# 1_Airframe-Power_1.net
KiCad netlist of a schematic drawn in Altium Designer
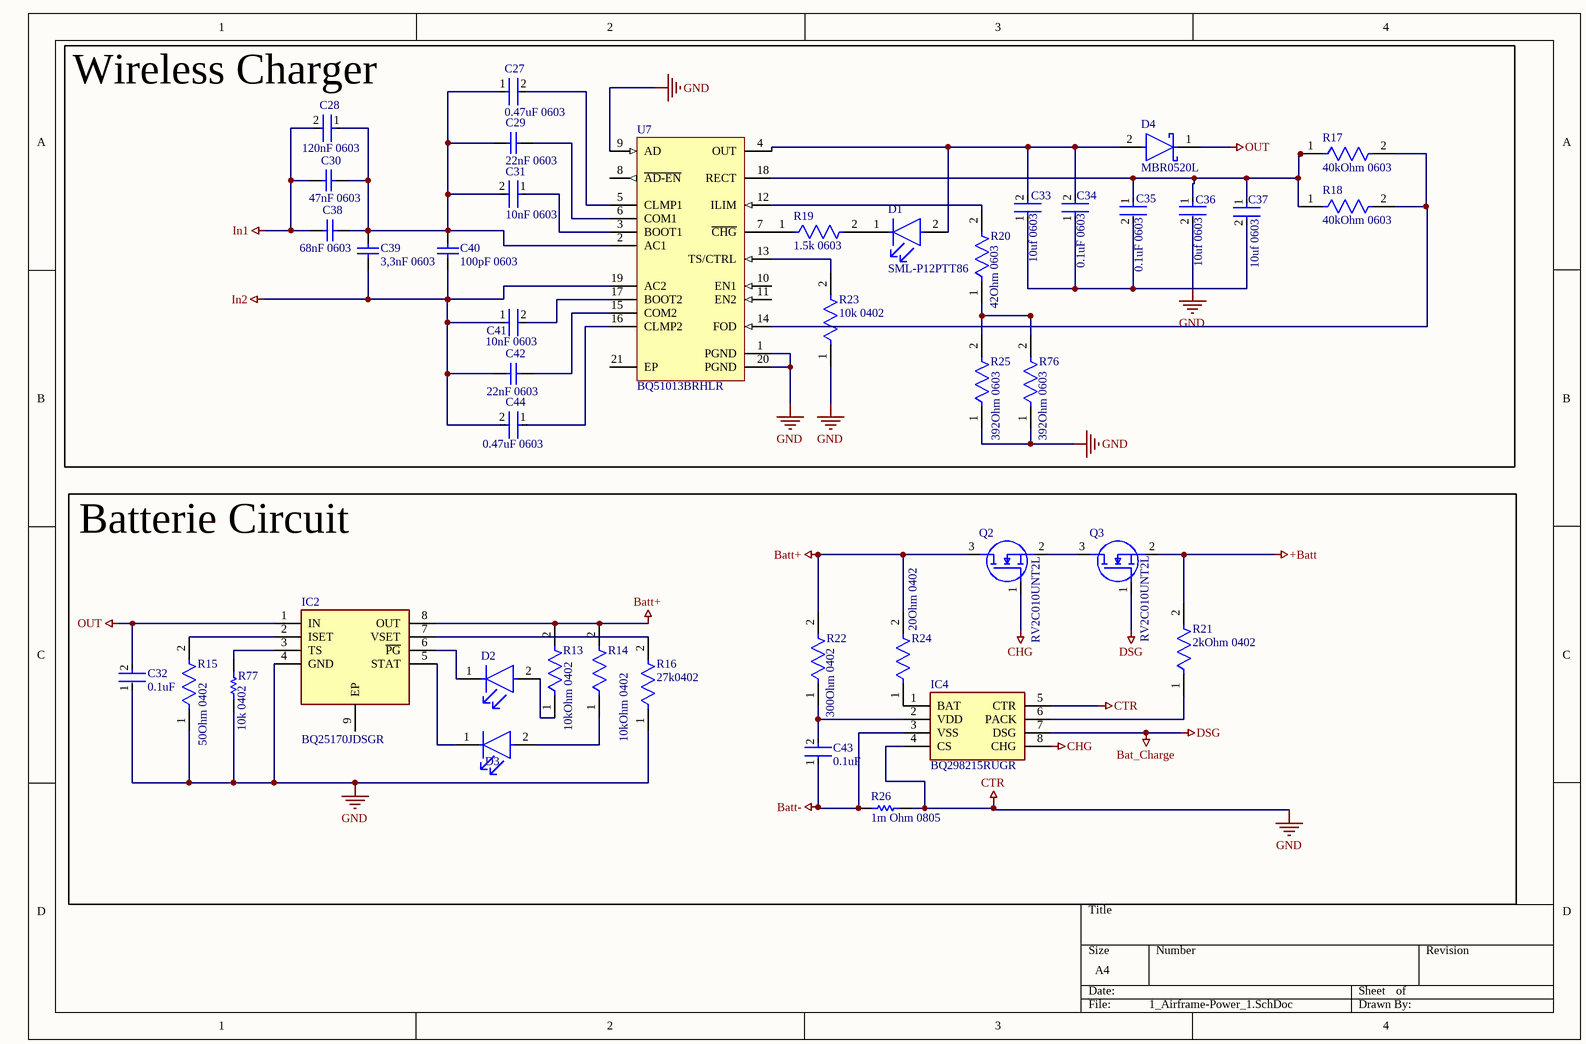
[diagram p0: 1_Airframe-Power_1.SchDoc]

(export (version "E")
  (design (tool "Eeschema 10.0.6"))
  (components
    (comp (ref "C27")
      (value "0.47uF 0603")
      (footprint "FP-GRM188-0_1-e0_2_0_5-IPC_A")
      (description "Chip Multilayer Ceramic Capacitors for General Purpose, 0603, 0.47uF, X7R, 15%, 10%, 16V")
      (fields (field (name "VOLTAGE") "16V") (field (name "TOLERANCE") "10%"))
      (libsource (lib "Altium Content Vault") (part "11868f565c42a9108669ba33697ecf6"))
    )
    (comp (ref "C28")
      (value "120nF 0603")
      (footprint "FP-C0603C-CF-MFG")
      (description "0603 C 120nF Ceramic Multilayer Capacitor; 50 V; +125degC; X7R Dielec; +/-10%")
      (fields (field (name "MANUFACTURER") "KEMET") (field (name "TOLERANCE") "0.1"))
      (libsource (lib "Altium Content Vault") (part "b4654b650e69147ec39a6b967a45e02"))
    )
    (comp (ref "C29")
      (value "22nF 0603")
      (footprint "CAPC1608X90X35ML10T15")
      (fields (field (name "MANUFACTURER") "Murata") (field (name "PART NUMBER") "GRM188R71H223KA01D"))
      (libsource (lib "Altium Content Vault") (part "CAP"))
    )
    (comp (ref "C30")
      (value "47nF 0603")
      (footprint "CAPC1608X90X35ML10T15")
      (fields (field (name "MANUFACTURER") "Murata") (field (name "PART NUMBER") "GRM188R71H473KA61D"))
      (libsource (lib "Altium Content Vault") (part "CAP"))
    )
    (comp (ref "C31")
      (value "10nF 0603")
      (footprint "FP-CC0603-DA-MFG")
      (description "CAP CER 10000PF 50V X7R 0603")
      (fields (field (name "TOLERANCE") "0.1") (field (name "MANUFACTURER PART NUMBER") "CC0603KRX7R9BB103"))
      (libsource (lib "Altium Content Vault") (part "11868f565c42a9108669ba33697ecf6"))
    )
    (comp (ref "C32")
      (value "0.1uF")
      (footprint "FP-GRM15-MFG")
      (description "CAP CER 0.1UF 16V X7R 0402")
      (fields (field (name "MANUFACTURER PART NUMBER") "GRM155R71C104KA88D") (field (name "TOLERANCE") "10%"))
      (libsource (lib "Altium Content Vault") (part "236180d848d6139a670b325ea6854c9"))
    )
    (comp (ref "C33")
      (value "10uf 0603")
      (footprint "FP-GRM188-0_1-e0_2_0_55-IPC_C")
      (description "Chip Multilayer Ceramic Capacitors for General Purpose, 0603, 10uF, X5R, 15%, 20%, 6.3V")
      (fields (field (name "VOLTAGE") "6.3V") (field (name "TOLERANCE") "20%"))
      (libsource (lib "Altium Content Vault") (part "02cd4be3c70576c341d710602a673aa"))
    )
    (comp (ref "C34")
      (value "0.1uF 0603")
      (footprint "FP-C0603C-CF-MFG")
      (description "CAP CER 0.1UF 50V X7R 0603")
      (fields (field (name "TOLERANCE") "0.1") (field (name "MANUFACTURER") "KEMET"))
      (libsource (lib "Altium Content Vault") (part "b4654b650e69147ec39a6b967a45e02"))
    )
    (comp (ref "C35")
      (value "0.1uF 0603")
      (footprint "FP-C0603C-CF-MFG")
      (description "CAP CER 0.1UF 50V X7R 0603")
      (fields (field (name "TOLERANCE") "0.1") (field (name "MANUFACTURER") "KEMET"))
      (libsource (lib "Altium Content Vault") (part "b4654b650e69147ec39a6b967a45e02"))
    )
    (comp (ref "C36")
      (value "10uf 0603")
      (footprint "FP-GRM188-0_1-e0_2_0_55-IPC_C")
      (description "Chip Multilayer Ceramic Capacitors for General Purpose, 0603, 10uF, X5R, 15%, 20%, 6.3V")
      (fields (field (name "VOLTAGE") "6.3V") (field (name "TOLERANCE") "20%"))
      (libsource (lib "Altium Content Vault") (part "02cd4be3c70576c341d710602a673aa"))
    )
    (comp (ref "C37")
      (value "10uf 0603")
      (footprint "FP-GRM188-0_1-e0_2_0_55-IPC_C")
      (description "Chip Multilayer Ceramic Capacitors for General Purpose, 0603, 10uF, X5R, 15%, 20%, 6.3V")
      (fields (field (name "VOLTAGE") "6.3V") (field (name "TOLERANCE") "20%"))
      (libsource (lib "Altium Content Vault") (part "02cd4be3c70576c341d710602a673aa"))
    )
    (comp (ref "C38")
      (value "68nF 0603")
      (footprint "CAPC1608X90X35LL10T15")
      (fields (field (name "PART NUMBER") "GRM188R71H683KA93D") (field (name "MANUFACTURER") "Murata"))
      (libsource (lib "Altium Content Vault") (part "CAP"))
    )
    (comp (ref "C39")
      (value "3,3nF 0603")
      (footprint "CAPC1608X90X35LL10T15")
      (fields (field (name "MANUFACTURER") "Murata") (field (name "PART NUMBER") "GRM188R71H332KA01D"))
      (libsource (lib "Altium Content Vault") (part "CAP"))
    )
    (comp (ref "C40")
      (value "100pF 0603")
      (footprint "CAPC1608X90X35NL10T15")
      (fields (field (name "PART NUMBER") "GRM1885C1H101JA01D") (field (name "MANUFACTURER") "Murata"))
      (libsource (lib "Altium Content Vault") (part "CAP"))
    )
    (comp (ref "C41")
      (value "10nF 0603")
      (footprint "FP-CC0603-DA-MFG")
      (description "CAP CER 10000PF 50V X7R 0603")
      (fields (field (name "TOLERANCE") "0.1") (field (name "MANUFACTURER PART NUMBER") "CC0603KRX7R9BB103"))
      (libsource (lib "Altium Content Vault") (part "11868f565c42a9108669ba33697ecf6"))
    )
    (comp (ref "C42")
      (value "22nF 0603")
      (footprint "CAPC1608X90X35ML10T15")
      (fields (field (name "MANUFACTURER") "Murata") (field (name "PART NUMBER") "GRM188R71H223KA01D"))
      (libsource (lib "Altium Content Vault") (part "CAP"))
    )
    (comp (ref "C43")
      (value "0.1uF")
      (footprint "FP-GRM15-MFG")
      (description "CAP CER 0.1UF 16V X7R 0402")
      (fields (field (name "MANUFACTURER PART NUMBER") "GRM155R71C104KA88D") (field (name "TOLERANCE") "10%"))
      (libsource (lib "Altium Content Vault") (part "236180d848d6139a670b325ea6854c9"))
    )
    (comp (ref "C44")
      (value "0.47uF 0603")
      (footprint "FP-GRM188-0_1-e0_2_0_5-IPC_A")
      (description "Chip Multilayer Ceramic Capacitors for General Purpose, 0603, 0.47uF, X7R, 15%, 10%, 16V")
      (fields (field (name "VOLTAGE") "16V") (field (name "TOLERANCE") "10%"))
      (libsource (lib "Altium Content Vault") (part "11868f565c42a9108669ba33697ecf6"))
    )
    (comp (ref "D1")
      (value "SML-P12PTT86")
      (footprint "FP-SML-P1-MFG")
      (description "LED GREEN CLEAR 1006 SMD")
      (fields
        (field (name "MANUFACTURER") "Rohm")
        (field (name "OCTOPART") "https://octopart.com/sml-p12ptt86-rohm-9290705")
      )
      (libsource (lib "Altium Content Vault") (part "8706943c75ba83719d021d2fdc84c58"))
    )
    (comp (ref "D2")
      (value "SML-P12PTT86")
      (footprint "FP-SML-P1-MFG")
      (description "LED GREEN CLEAR 1006 SMD")
      (fields
        (field (name "MANUFACTURER") "Rohm")
        (field (name "OCTOPART") "https://octopart.com/sml-p12ptt86-rohm-9290705")
      )
      (libsource (lib "Altium Content Vault") (part "8706943c75ba83719d021d2fdc84c58"))
    )
    (comp (ref "D3")
      (value "SML-P12PTT86")
      (footprint "FP-SML-P1-MFG")
      (description "LED GREEN CLEAR 1006 SMD")
      (fields
        (field (name "MANUFACTURER") "Rohm")
        (field (name "OCTOPART") "https://octopart.com/sml-p12ptt86-rohm-9290705")
      )
      (libsource (lib "Altium Content Vault") (part "8706943c75ba83719d021d2fdc84c58"))
    )
    (comp (ref "D4")
      (value "MBR0520L")
      (footprint "FP-MA02A-MFG")
      (description "DIODE SCHOTTKY 20V 500MA SOD123")
      (libsource (lib "Altium Content Vault") (part "1d6ec82d83fb6aee721767c19dac4b9"))
    )
    (comp (ref "IC2")
      (value "BQ25170JDSGR")
      (footprint "SamacSys:SON50P200X200X80-9N")
      (description "Integrated Circuit")
      (fields (field (name "MOUSER PART NUMBER") "595-BQ25170JDSGR"))
      (libsource (lib "*") (part "BQ25170JDSGR"))
    )
    (comp (ref "IC4")
      (value "BQ298215RUGR")
      (footprint "SamacSys:BQ298215RUGR")
      (description "Integrated Circuit")
      (fields (field (name "MOUSER PART NUMBER") "595-BQ298215RUGR"))
      (libsource (lib "*") (part "BQ298215RUGR"))
    )
    (comp (ref "Q2")
      (value "RV2C010UNT2L")
      (footprint "SamacSys:RV2C010UNT2L")
      (description "MOSFET (N-Channel)")
      (fields (field (name "MOUSER PART NUMBER") "755-RV2C010UNT2L"))
      (libsource (lib "*") (part "RV2C010UNT2L"))
    )
    (comp (ref "Q3")
      (value "RV2C010UNT2L")
      (footprint "SamacSys:RV2C010UNT2L")
      (description "MOSFET (N-Channel)")
      (fields (field (name "MOUSER PART NUMBER") "755-RV2C010UNT2L"))
      (libsource (lib "*") (part "RV2C010UNT2L"))
    )
    (comp (ref "R13")
      (value "10kOhm 0402")
      (footprint "FP-CRCW0402-e3-IPC_C")
      (fields (field (name "TOLERANCE") "1%"))
      (libsource (lib "Altium Content Vault") (part "1029c3af85768c4190bb7ad29bc67b5"))
    )
    (comp (ref "R14")
      (value "10kOhm 0402")
      (footprint "FP-CRCW0402-e3-IPC_C")
      (fields (field (name "TOLERANCE") "1%"))
      (libsource (lib "Altium Content Vault") (part "1029c3af85768c4190bb7ad29bc67b5"))
    )
    (comp (ref "R15")
      (value "50Ohm 0402")
      (footprint "FP-CRCW0402-e3-IPC_C")
      (description "600Ohm 0402")
      (fields (field (name "TOLERANCE") "1%"))
      (libsource (lib "Altium Content Vault") (part "1029c3af85768c4190bb7ad29bc67b5"))
    )
    (comp (ref "R16")
      (value "27k0402")
      (footprint "FP-CRCW0402-e3-IPC_C")
      (description "27kOhm 0402")
      (fields (field (name "TOLERANCE") "1%"))
      (libsource (lib "Altium Content Vault") (part "1029c3af85768c4190bb7ad29bc67b5"))
    )
    (comp (ref "R17")
      (value "40kOhm 0603")
      (footprint "FP-CRCW0402-e3-IPC_C")
      (description "392Ohm 0603")
      (fields (field (name "TOLERANCE") "5%"))
      (libsource (lib "Altium Content Vault") (part "1029c3af85768c4190bb7ad29bc67b5"))
    )
    (comp (ref "R18")
      (value "40kOhm 0603")
      (footprint "FP-CRCW0402-e3-IPC_C")
      (description "392Ohm 0603")
      (fields (field (name "TOLERANCE") "5%"))
      (libsource (lib "Altium Content Vault") (part "1029c3af85768c4190bb7ad29bc67b5"))
    )
    (comp (ref "R19")
      (value "1.5k 0603")
      (footprint "FP-CRCW0402-e3-IPC_C")
      (fields (field (name "TOLERANCE") "5%"))
      (libsource (lib "Altium Content Vault") (part "1029c3af85768c4190bb7ad29bc67b5"))
    )
    (comp (ref "R20")
      (value "42Ohm 0603")
      (footprint "FP-CRCW0402-e3-IPC_C")
      (fields (field (name "TOLERANCE") "5%"))
      (libsource (lib "Altium Content Vault") (part "1029c3af85768c4190bb7ad29bc67b5"))
    )
    (comp (ref "R21")
      (value "2kOhm 0402")
      (footprint "FP-CRCW0402-e3-IPC_C")
      (fields (field (name "TOLERANCE") "1%"))
      (libsource (lib "Altium Content Vault") (part "1029c3af85768c4190bb7ad29bc67b5"))
    )
    (comp (ref "R22")
      (value "300Ohm 0402")
      (footprint "FP-CRCW0402-e3-IPC_C")
      (fields (field (name "TOLERANCE") "1%"))
      (libsource (lib "Altium Content Vault") (part "1029c3af85768c4190bb7ad29bc67b5"))
    )
    (comp (ref "R23")
      (value "10k 0402")
      (footprint "FP-CRCW0402-e3-IPC_B")
      (fields (field (name "TOLERANCE") "1%"))
      (libsource (lib "Altium Content Vault") (part "1029c3af85768c4190bb7ad29bc67b5"))
    )
    (comp (ref "R24")
      (value "20Ohm 0402")
      (footprint "FP-CRCW0402-e3-IPC_C")
      (fields (field (name "TOLERANCE") "1%"))
      (libsource (lib "Altium Content Vault") (part "1029c3af85768c4190bb7ad29bc67b5"))
    )
    (comp (ref "R25")
      (value "392Ohm 0603")
      (footprint "FP-CRCW0402-e3-IPC_C")
      (fields (field (name "TOLERANCE") "5%"))
      (libsource (lib "Altium Content Vault") (part "1029c3af85768c4190bb7ad29bc67b5"))
    )
    (comp (ref "R26")
      (value "1m Ohm 0805")
      (footprint "RESC1609X50X30LL10T20")
      (fields (field (name "MANUFACTURER") "Vishay Dale") (field (name "PART NUMBER") "CRCW06031R00FKEA"))
      (libsource (lib "Altium Content Vault") (part "RES"))
    )
    (comp (ref "R76")
      (value "392Ohm 0603")
      (footprint "FP-CRCW0402-e3-IPC_C")
      (fields (field (name "TOLERANCE") "5%"))
      (libsource (lib "Altium Content Vault") (part "1029c3af85768c4190bb7ad29bc67b5"))
    )
    (comp (ref "R77")
      (value "10k 0402")
      (footprint "RESC1608X55X25ML10T15")
      (fields (field (name "TOLERANCE") "5%") (field (name "MANUFACTURER") "Yageo"))
      (libsource (lib "Altium Content Vault") (part "RES-2"))
    )
    (comp (ref "U7")
      (value "BQ51013BRHLR")
      (footprint "RHL0020A_V")
      (fields (field (name "PARTNUMBER") "BQ51013B"))
      (libsource (lib "Altium Content Vault") (part "TI-BQ51013B-RHL20"))
    )
  )
  (nets
    (net (code "1") (name "+Batt") (class "Default")
      (node (ref "Q3") (pin "2") (pinfunction "S_2") (pintype "passive"))
      (node (ref "R21") (pin "2") (pinfunction "2_2") (pintype "passive"))
    )
    (net (code "2") (name "Bat_Charge") (class "Default")
      (node (ref "IC4") (pin "7") (pinfunction "DSG_7") (pintype "passive"))
      (node (ref "Q3") (pin "1") (pinfunction "G_1") (pintype "passive"))
    )
    (net (code "3") (name "Batt+") (class "Default")
      (node (ref "IC2") (pin "8") (pinfunction "OUT_8") (pintype "passive"))
      (node (ref "Q2") (pin "3") (pinfunction "D_3") (pintype "passive"))
      (node (ref "R13") (pin "2") (pinfunction "2_2") (pintype "passive"))
      (node (ref "R14") (pin "2") (pinfunction "2_2") (pintype "passive"))
      (node (ref "R22") (pin "2") (pinfunction "2_2") (pintype "passive"))
      (node (ref "R24") (pin "2") (pinfunction "2_2") (pintype "passive"))
    )
    (net (code "4") (name "Batt-") (class "Default")
      (node (ref "C43") (pin "1") (pinfunction "1_1") (pintype "passive"))
      (node (ref "IC4") (pin "3") (pinfunction "VSS_3") (pintype "passive"))
      (node (ref "R26") (pin "1") (pinfunction "1_1") (pintype "passive"))
    )
    (net (code "5") (name "CHG") (class "Default")
      (node (ref "IC4") (pin "8") (pinfunction "CHG_8") (pintype "passive"))
      (node (ref "Q2") (pin "1") (pinfunction "G_1") (pintype "passive"))
    )
    (net (code "6") (name "CTR") (class "Default")
      (node (ref "C32") (pin "1") (pinfunction "1_1") (pintype "passive"))
      (node (ref "C36") (pin "2") (pinfunction "2_2") (pintype "passive"))
      (node (ref "IC2") (pin "4") (pinfunction "GND_4") (pintype "passive"))
      (node (ref "IC4") (pin "4") (pinfunction "CS_4") (pintype "passive"))
      (node (ref "IC4") (pin "5") (pinfunction "CTR_5") (pintype "passive"))
      (node (ref "R15") (pin "1") (pinfunction "1_1") (pintype "passive"))
      (node (ref "R16") (pin "1") (pinfunction "1_1") (pintype "passive"))
      (node (ref "R23") (pin "1") (pinfunction "1_1") (pintype "passive"))
      (node (ref "R25") (pin "1") (pinfunction "1_1") (pintype "passive"))
      (node (ref "R26") (pin "2") (pinfunction "2_2") (pintype "passive"))
      (node (ref "R76") (pin "1") (pinfunction "1_1") (pintype "passive"))
      (node (ref "R77") (pin "2") (pinfunction "2_2") (pintype "passive"))
      (node (ref "U7") (pin "1") (pinfunction "PGND_1") (pintype "power_in"))
      (node (ref "U7") (pin "20") (pinfunction "PGND_20") (pintype "power_in"))
      (node (ref "U7") (pin "9") (pinfunction "AD_9") (pintype "input"))
    )
    (net (code "7") (name "In1") (class "Default")
      (node (ref "C28") (pin "2") (pinfunction "2_2") (pintype "passive"))
      (node (ref "C30") (pin "1") (pinfunction "1_1") (pintype "passive"))
      (node (ref "C38") (pin "1") (pinfunction "1_1") (pintype "passive"))
    )
    (net (code "8") (name "In2") (class "Default")
      (node (ref "C39") (pin "1") (pinfunction "1_1") (pintype "passive"))
      (node (ref "C40") (pin "1") (pinfunction "1_1") (pintype "passive"))
      (node (ref "C41") (pin "1") (pinfunction "1_1") (pintype "passive"))
      (node (ref "C42") (pin "2") (pinfunction "2_2") (pintype "passive"))
      (node (ref "C44") (pin "2") (pinfunction "2_2") (pintype "passive"))
      (node (ref "U7") (pin "19") (pinfunction "AC2_19") (pintype "power_in"))
    )
    (net (code "9") (name "Net-(C33-Pad1)") (class "Default")
      (node (ref "C33") (pin "1") (pinfunction "1_1") (pintype "passive"))
      (node (ref "C34") (pin "1") (pinfunction "1_1") (pintype "passive"))
      (node (ref "C35") (pin "2") (pinfunction "2_2") (pintype "passive"))
      (node (ref "C37") (pin "2") (pinfunction "2_2") (pintype "passive"))
    )
    (net (code "10") (name "Net-(D1-A)") (class "Default")
      (node (ref "C33") (pin "2") (pinfunction "2_2") (pintype "passive"))
      (node (ref "C34") (pin "2") (pinfunction "2_2") (pintype "passive"))
      (node (ref "D1") (pin "2") (pinfunction "A_2") (pintype "passive"))
      (node (ref "D4") (pin "2") (pinfunction "A_2") (pintype "passive"))
      (node (ref "U7") (pin "4") (pinfunction "OUT_4") (pintype "power_in"))
    )
    (net (code "11") (name "Net-(D1-C)") (class "Default")
      (node (ref "D1") (pin "1") (pinfunction "C_1") (pintype "passive"))
      (node (ref "R19") (pin "2") (pinfunction "2_2") (pintype "passive"))
    )
    (net (code "12") (name "Net-(D2-A)") (class "Default")
      (node (ref "D2") (pin "2") (pinfunction "A_2") (pintype "passive"))
      (node (ref "R13") (pin "1") (pinfunction "1_1") (pintype "passive"))
    )
    (net (code "13") (name "Net-(D2-C)") (class "Default")
      (node (ref "D2") (pin "1") (pinfunction "C_1") (pintype "passive"))
      (node (ref "IC2") (pin "6") (pinfunction "~{PG}_6") (pintype "passive"))
    )
    (net (code "14") (name "Net-(D3-A)") (class "Default")
      (node (ref "D3") (pin "2") (pinfunction "A_2") (pintype "passive"))
      (node (ref "R14") (pin "1") (pinfunction "1_1") (pintype "passive"))
    )
    (net (code "15") (name "Net-(D3-C)") (class "Default")
      (node (ref "D3") (pin "1") (pinfunction "C_1") (pintype "passive"))
      (node (ref "IC2") (pin "5") (pinfunction "STAT_5") (pintype "passive"))
    )
    (net (code "16") (name "Net-(IC2-ISET)") (class "Default")
      (node (ref "IC2") (pin "2") (pinfunction "ISET_2") (pintype "passive"))
      (node (ref "R15") (pin "2") (pinfunction "2_2") (pintype "passive"))
    )
    (net (code "17") (name "Net-(IC2-TS)") (class "Default")
      (node (ref "IC2") (pin "3") (pinfunction "TS_3") (pintype "passive"))
      (node (ref "R77") (pin "1") (pinfunction "1_1") (pintype "passive"))
    )
    (net (code "18") (name "Net-(IC2-VSET)") (class "Default")
      (node (ref "IC2") (pin "7") (pinfunction "VSET_7") (pintype "passive"))
      (node (ref "R16") (pin "2") (pinfunction "2_2") (pintype "passive"))
    )
    (net (code "19") (name "Net-(IC4-BAT)") (class "Default")
      (node (ref "IC4") (pin "1") (pinfunction "BAT_1") (pintype "passive"))
      (node (ref "R24") (pin "1") (pinfunction "1_1") (pintype "passive"))
    )
    (net (code "20") (name "Net-(IC4-PACK)") (class "Default")
      (node (ref "IC4") (pin "6") (pinfunction "PACK_6") (pintype "passive"))
      (node (ref "R21") (pin "1") (pinfunction "1_1") (pintype "passive"))
    )
    (net (code "21") (name "Net-(IC4-VDD)") (class "Default")
      (node (ref "C43") (pin "2") (pinfunction "2_2") (pintype "passive"))
      (node (ref "IC4") (pin "2") (pinfunction "VDD_2") (pintype "passive"))
      (node (ref "R22") (pin "1") (pinfunction "1_1") (pintype "passive"))
    )
    (net (code "22") (name "Net-(Q2-S)") (class "Default")
      (node (ref "Q2") (pin "2") (pinfunction "S_2") (pintype "passive"))
      (node (ref "Q3") (pin "3") (pinfunction "D_3") (pintype "passive"))
    )
    (net (code "23") (name "Net-(R20-Pad1)") (class "Default")
      (node (ref "R20") (pin "1") (pinfunction "1_1") (pintype "passive"))
      (node (ref "R25") (pin "2") (pinfunction "2_2") (pintype "passive"))
      (node (ref "R76") (pin "2") (pinfunction "2_2") (pintype "passive"))
    )
    (net (code "24") (name "Net-(U7-AC1)") (class "Default")
      (node (ref "C27") (pin "1") (pinfunction "1_1") (pintype "passive"))
      (node (ref "C28") (pin "1") (pinfunction "1_1") (pintype "passive"))
      (node (ref "C29") (pin "1") (pinfunction "1_1") (pintype "passive"))
      (node (ref "C30") (pin "2") (pinfunction "2_2") (pintype "passive"))
      (node (ref "C31") (pin "2") (pinfunction "2_2") (pintype "passive"))
      (node (ref "C38") (pin "2") (pinfunction "2_2") (pintype "passive"))
      (node (ref "C39") (pin "2") (pinfunction "2_2") (pintype "passive"))
      (node (ref "C40") (pin "2") (pinfunction "2_2") (pintype "passive"))
      (node (ref "U7") (pin "2") (pinfunction "AC1_2") (pintype "power_in"))
    )
    (net (code "25") (name "Net-(U7-BOOT1)") (class "Default")
      (node (ref "C31") (pin "1") (pinfunction "1_1") (pintype "passive"))
      (node (ref "U7") (pin "3") (pinfunction "BOOT1_3") (pintype "passive"))
    )
    (net (code "26") (name "Net-(U7-BOOT2)") (class "Default")
      (node (ref "C41") (pin "2") (pinfunction "2_2") (pintype "passive"))
      (node (ref "U7") (pin "17") (pinfunction "BOOT2_17") (pintype "passive"))
    )
    (net (code "27") (name "Net-(U7-CLMP1)") (class "Default")
      (node (ref "C27") (pin "2") (pinfunction "2_2") (pintype "passive"))
      (node (ref "U7") (pin "5") (pinfunction "CLMP1_5") (pintype "open_collector"))
    )
    (net (code "28") (name "Net-(U7-CLMP2)") (class "Default")
      (node (ref "C44") (pin "1") (pinfunction "1_1") (pintype "passive"))
      (node (ref "U7") (pin "16") (pinfunction "CLMP2_16") (pintype "open_collector"))
    )
    (net (code "29") (name "Net-(U7-COM1)") (class "Default")
      (node (ref "C29") (pin "2") (pinfunction "2_2") (pintype "passive"))
      (node (ref "U7") (pin "6") (pinfunction "COM1_6") (pintype "open_collector"))
    )
    (net (code "30") (name "Net-(U7-COM2)") (class "Default")
      (node (ref "C42") (pin "1") (pinfunction "1_1") (pintype "passive"))
      (node (ref "U7") (pin "15") (pinfunction "COM2_15") (pintype "open_collector"))
    )
    (net (code "31") (name "Net-(U7-FOD)") (class "Default")
      (node (ref "R17") (pin "2") (pinfunction "2_2") (pintype "passive"))
      (node (ref "R18") (pin "2") (pinfunction "2_2") (pintype "passive"))
      (node (ref "U7") (pin "14") (pinfunction "FOD_14") (pintype "input"))
    )
    (net (code "32") (name "Net-(U7-ILIM)") (class "Default")
      (node (ref "R20") (pin "2") (pinfunction "2_2") (pintype "passive"))
      (node (ref "U7") (pin "12") (pinfunction "ILIM_12") (pintype "input"))
    )
    (net (code "33") (name "Net-(U7-RECT)") (class "Default")
      (node (ref "C35") (pin "1") (pinfunction "1_1") (pintype "passive"))
      (node (ref "C36") (pin "1") (pinfunction "1_1") (pintype "passive"))
      (node (ref "C37") (pin "1") (pinfunction "1_1") (pintype "passive"))
      (node (ref "R17") (pin "1") (pinfunction "1_1") (pintype "passive"))
      (node (ref "R18") (pin "1") (pinfunction "1_1") (pintype "passive"))
      (node (ref "U7") (pin "18") (pinfunction "RECT_18") (pintype "passive"))
    )
    (net (code "34") (name "Net-(U7-TS{slash}CTRL)") (class "Default")
      (node (ref "R23") (pin "2") (pinfunction "2_2") (pintype "passive"))
      (node (ref "U7") (pin "13") (pinfunction "TS/CTRL_13") (pintype "input"))
    )
    (net (code "35") (name "Net-(U7-~{CHG})") (class "Default")
      (node (ref "R19") (pin "1") (pinfunction "1_1") (pintype "passive"))
      (node (ref "U7") (pin "7") (pinfunction "~{CHG}_7") (pintype "open_collector"))
    )
    (net (code "36") (name "OUT") (class "Default")
      (node (ref "C32") (pin "2") (pinfunction "2_2") (pintype "passive"))
      (node (ref "D4") (pin "1") (pinfunction "C_1") (pintype "passive"))
      (node (ref "IC2") (pin "1") (pinfunction "IN_1") (pintype "passive"))
    )
    (net (code "37") (name "unconnected-(IC2-EP-Pad9)") (class "Default")
      (node (ref "IC2") (pin "9") (pinfunction "EP_9") (pintype "passive"))
    )
    (net (code "38") (name "unconnected-(U7-EN1-Pad10)") (class "Default")
      (node (ref "U7") (pin "10") (pinfunction "EN1_10") (pintype "input"))
    )
    (net (code "39") (name "unconnected-(U7-EN2-Pad11)") (class "Default")
      (node (ref "U7") (pin "11") (pinfunction "EN2_11") (pintype "input"))
    )
    (net (code "40") (name "unconnected-(U7-EP-Pad21)") (class "Default")
      (node (ref "U7") (pin "21") (pinfunction "EP_21") (pintype "passive"))
    )
    (net (code "41") (name "unconnected-(U7-~{AD-EN}-Pad8)") (class "Default")
      (node (ref "U7") (pin "8") (pinfunction "~{AD-EN}_8") (pintype "output"))
    )
  )
)
